# Groupe7.net
KiCad netlist of a schematic drawn in EAGLE
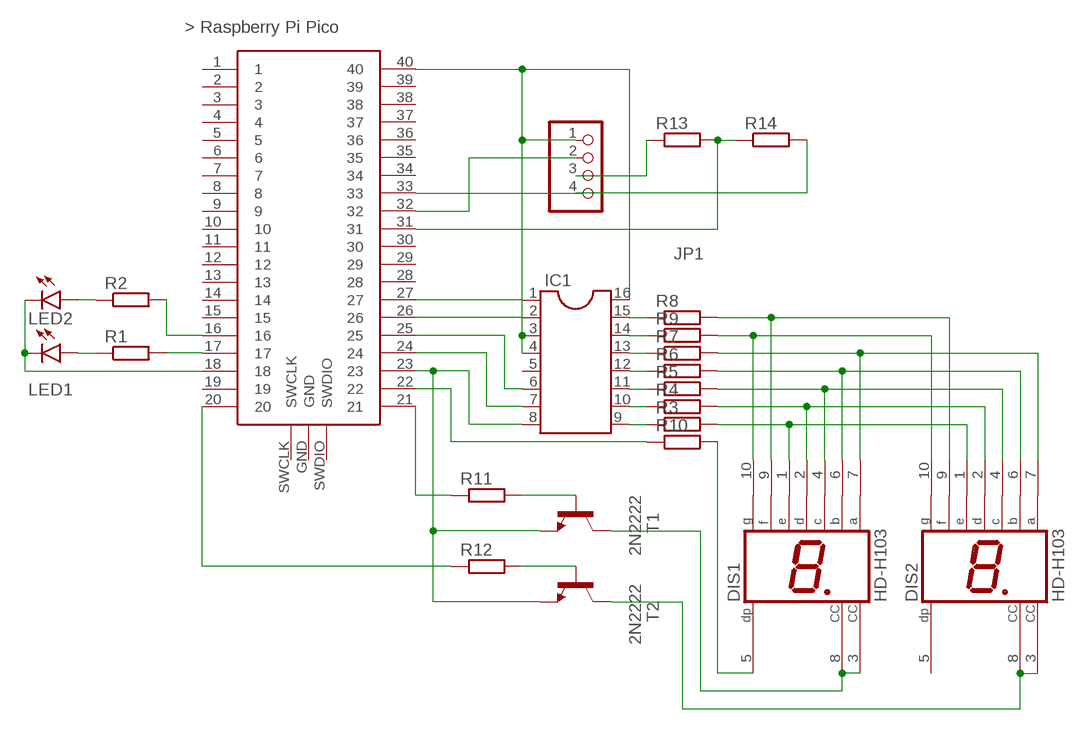
[diagram p0: schematic, sheet 1]

(export (version "E")
  (design (tool "Eeschema 10.0.6"))
  (components
    (comp (ref "DIS1")
      (value "HD-H103")
      (footprint "eagle-import:HDSP-M")
      (libsource (lib "eagle-import") (part "HD-H103"))
    )
    (comp (ref "DIS2")
      (value "HD-H103")
      (footprint "eagle-import:HDSP-M")
      (libsource (lib "eagle-import") (part "HD-H103"))
    )
    (comp (ref "IC1")
      (value "DIL16")
      (footprint "eagle-import:DIL16")
      (libsource (lib "eagle-import") (part "DIL16"))
    )
    (comp (ref "JP1")
      (value "PINHD-1X4")
      (footprint "eagle-import:1X04")
      (libsource (lib "eagle-import") (part "PINHD-1X4"))
    )
    (comp (ref "LED1")
      (value "LED5MM")
      (footprint "eagle-import:LED5MM")
      (libsource (lib "eagle-import") (part "LED5MM"))
    )
    (comp (ref "LED2")
      (value "LED5MM")
      (footprint "eagle-import:LED5MM")
      (libsource (lib "eagle-import") (part "LED5MM"))
    )
    (comp (ref "R1")
      (value "R-EU_0207/7")
      (footprint "eagle-import:0207_7")
      (libsource (lib "eagle-import") (part "R-EU_0207/7"))
    )
    (comp (ref "R2")
      (value "R-EU_0207/7")
      (footprint "eagle-import:0207_7")
      (libsource (lib "eagle-import") (part "R-EU_0207/7"))
    )
    (comp (ref "R3")
      (value "R-EU_0207/7")
      (footprint "eagle-import:0207_7")
      (libsource (lib "eagle-import") (part "R-EU_0207/7"))
    )
    (comp (ref "R4")
      (value "R-EU_0207/7")
      (footprint "eagle-import:0207_7")
      (libsource (lib "eagle-import") (part "R-EU_0207/7"))
    )
    (comp (ref "R5")
      (value "R-EU_0207/7")
      (footprint "eagle-import:0207_7")
      (libsource (lib "eagle-import") (part "R-EU_0207/7"))
    )
    (comp (ref "R6")
      (value "R-EU_0207/7")
      (footprint "eagle-import:0207_7")
      (libsource (lib "eagle-import") (part "R-EU_0207/7"))
    )
    (comp (ref "R7")
      (value "R-EU_0207/7")
      (footprint "eagle-import:0207_7")
      (libsource (lib "eagle-import") (part "R-EU_0207/7"))
    )
    (comp (ref "R8")
      (value "R-EU_0207/7")
      (footprint "eagle-import:0207_7")
      (libsource (lib "eagle-import") (part "R-EU_0207/7"))
    )
    (comp (ref "R9")
      (value "R-EU_0207/7")
      (footprint "eagle-import:0207_7")
      (libsource (lib "eagle-import") (part "R-EU_0207/7"))
    )
    (comp (ref "R10")
      (value "R-EU_0207/7")
      (footprint "eagle-import:0207_7")
      (libsource (lib "eagle-import") (part "R-EU_0207/7"))
    )
    (comp (ref "R11")
      (value "R-EU_0207/7")
      (footprint "eagle-import:0207_7")
      (libsource (lib "eagle-import") (part "R-EU_0207/7"))
    )
    (comp (ref "R12")
      (value "R-EU_0207/7")
      (footprint "eagle-import:0207_7")
      (libsource (lib "eagle-import") (part "R-EU_0207/7"))
    )
    (comp (ref "R13")
      (value "R-EU_0207/7")
      (footprint "eagle-import:0207_7")
      (libsource (lib "eagle-import") (part "R-EU_0207/7"))
    )
    (comp (ref "R14")
      (value "R-EU_0207/7")
      (footprint "eagle-import:0207_7")
      (libsource (lib "eagle-import") (part "R-EU_0207/7"))
    )
    (comp (ref "T1")
      (value "2N2222")
      (footprint "eagle-import:TO18")
      (libsource (lib "eagle-import") (part "2N2222"))
    )
    (comp (ref "T2")
      (value "2N2222")
      (footprint "eagle-import:TO18")
      (libsource (lib "eagle-import") (part "2N2222"))
    )
    (comp (ref "U$1")
      (value "RASPBERRY-PI-PICO_TH")
      (footprint "eagle-import:FT_RASPBERRY-PI-PICO_TH")
      (libsource (lib "eagle-import") (part "RASPBERRY-PI-PICO_TH"))
    )
  )
  (nets
    (net (code "1") (name "Net-(DIS1-A)") (class "Default")
      (node (ref "DIS1") (pin "7") (pinfunction "A_7") (pintype "passive"))
      (node (ref "DIS2") (pin "7") (pinfunction "A_7") (pintype "passive"))
      (node (ref "R7") (pin "2") (pinfunction "2_2") (pintype "passive"))
    )
    (net (code "2") (name "Net-(DIS1-B)") (class "Default")
      (node (ref "DIS1") (pin "6") (pinfunction "B_6") (pintype "passive"))
      (node (ref "DIS2") (pin "6") (pinfunction "B_6") (pintype "passive"))
      (node (ref "R6") (pin "2") (pinfunction "2_2") (pintype "passive"))
    )
    (net (code "3") (name "Net-(DIS1-C)") (class "Default")
      (node (ref "DIS1") (pin "4") (pinfunction "C_4") (pintype "passive"))
      (node (ref "DIS2") (pin "4") (pinfunction "C_4") (pintype "passive"))
      (node (ref "R5") (pin "2") (pinfunction "2_2") (pintype "passive"))
    )
    (net (code "4") (name "Net-(DIS1-D)") (class "Default")
      (node (ref "DIS1") (pin "2") (pinfunction "D_2") (pintype "passive"))
      (node (ref "DIS2") (pin "2") (pinfunction "D_2") (pintype "passive"))
      (node (ref "R4") (pin "2") (pinfunction "2_2") (pintype "passive"))
    )
    (net (code "5") (name "Net-(DIS1-DP)") (class "Default")
      (node (ref "DIS1") (pin "5") (pinfunction "DP_5") (pintype "passive"))
      (node (ref "R10") (pin "2") (pinfunction "2_2") (pintype "passive"))
    )
    (net (code "6") (name "Net-(DIS1-E)") (class "Default")
      (node (ref "DIS1") (pin "1") (pinfunction "E_1") (pintype "passive"))
      (node (ref "DIS2") (pin "1") (pinfunction "E_1") (pintype "passive"))
      (node (ref "R3") (pin "2") (pinfunction "2_2") (pintype "passive"))
    )
    (net (code "7") (name "Net-(DIS1-F)") (class "Default")
      (node (ref "DIS1") (pin "9") (pinfunction "F_9") (pintype "passive"))
      (node (ref "DIS2") (pin "9") (pinfunction "F_9") (pintype "passive"))
      (node (ref "R8") (pin "2") (pinfunction "2_2") (pintype "passive"))
    )
    (net (code "8") (name "Net-(DIS1-G)") (class "Default")
      (node (ref "DIS1") (pin "10") (pinfunction "G_10") (pintype "passive"))
      (node (ref "DIS2") (pin "10") (pinfunction "G_10") (pintype "passive"))
      (node (ref "R9") (pin "2") (pinfunction "2_2") (pintype "passive"))
    )
    (net (code "9") (name "Net-(IC1-Pad1)") (class "Default")
      (node (ref "IC1") (pin "1") (pinfunction "1_1") (pintype "passive"))
      (node (ref "U$1") (pin "27") (pinfunction "27_27") (pintype "bidirectional"))
    )
    (net (code "10") (name "Net-(IC1-Pad2)") (class "Default")
      (node (ref "IC1") (pin "2") (pinfunction "2_2") (pintype "passive"))
      (node (ref "U$1") (pin "26") (pinfunction "26_26") (pintype "bidirectional"))
    )
    (net (code "11") (name "Net-(IC1-Pad6)") (class "Default")
      (node (ref "IC1") (pin "6") (pinfunction "6_6") (pintype "passive"))
      (node (ref "U$1") (pin "25") (pinfunction "25_25") (pintype "bidirectional"))
    )
    (net (code "12") (name "Net-(IC1-Pad7)") (class "Default")
      (node (ref "IC1") (pin "7") (pinfunction "7_7") (pintype "passive"))
      (node (ref "U$1") (pin "24") (pinfunction "24_24") (pintype "bidirectional"))
    )
    (net (code "13") (name "Net-(IC1-Pad9)") (class "Default")
      (node (ref "IC1") (pin "9") (pinfunction "9_9") (pintype "passive"))
      (node (ref "R3") (pin "1") (pinfunction "1_1") (pintype "passive"))
    )
    (net (code "14") (name "Net-(IC1-Pad10)") (class "Default")
      (node (ref "IC1") (pin "10") (pinfunction "10_10") (pintype "passive"))
      (node (ref "R4") (pin "1") (pinfunction "1_1") (pintype "passive"))
    )
    (net (code "15") (name "Net-(IC1-Pad11)") (class "Default")
      (node (ref "IC1") (pin "11") (pinfunction "11_11") (pintype "passive"))
      (node (ref "R5") (pin "1") (pinfunction "1_1") (pintype "passive"))
    )
    (net (code "16") (name "Net-(IC1-Pad12)") (class "Default")
      (node (ref "IC1") (pin "12") (pinfunction "12_12") (pintype "passive"))
      (node (ref "R6") (pin "1") (pinfunction "1_1") (pintype "passive"))
    )
    (net (code "17") (name "Net-(IC1-Pad13)") (class "Default")
      (node (ref "IC1") (pin "13") (pinfunction "13_13") (pintype "passive"))
      (node (ref "R7") (pin "1") (pinfunction "1_1") (pintype "passive"))
    )
    (net (code "18") (name "Net-(IC1-Pad14)") (class "Default")
      (node (ref "IC1") (pin "14") (pinfunction "14_14") (pintype "passive"))
      (node (ref "R9") (pin "1") (pinfunction "1_1") (pintype "passive"))
    )
    (net (code "19") (name "Net-(IC1-Pad15)") (class "Default")
      (node (ref "IC1") (pin "15") (pinfunction "15_15") (pintype "passive"))
      (node (ref "R8") (pin "1") (pinfunction "1_1") (pintype "passive"))
    )
    (net (code "20") (name "Net-(IC1-Pad16)") (class "Default")
      (node (ref "IC1") (pin "16") (pinfunction "16_16") (pintype "passive"))
      (node (ref "IC1") (pin "3") (pinfunction "3_3") (pintype "passive"))
      (node (ref "IC1") (pin "4") (pinfunction "4_4") (pintype "passive"))
      (node (ref "JP1") (pin "1") (pinfunction "1_1") (pintype "passive"))
      (node (ref "U$1") (pin "40") (pinfunction "40_40") (pintype "bidirectional"))
    )
    (net (code "21") (name "Net-(JP1-Pad2)") (class "Default")
      (node (ref "JP1") (pin "2") (pinfunction "2_2") (pintype "passive"))
      (node (ref "U$1") (pin "32") (pinfunction "32_32") (pintype "bidirectional"))
    )
    (net (code "22") (name "Net-(JP1-Pad3)") (class "Default")
      (node (ref "JP1") (pin "3") (pinfunction "3_3") (pintype "passive"))
      (node (ref "R13") (pin "1") (pinfunction "1_1") (pintype "passive"))
    )
    (net (code "23") (name "Net-(JP1-Pad4)") (class "Default")
      (node (ref "JP1") (pin "4") (pinfunction "4_4") (pintype "passive"))
      (node (ref "R14") (pin "2") (pinfunction "2_2") (pintype "passive"))
      (node (ref "U$1") (pin "33") (pinfunction "33_33") (pintype "bidirectional"))
    )
    (net (code "24") (name "Net-(LED1-C)") (class "Default")
      (node (ref "LED1") (pin "K") (pinfunction "C_K") (pintype "passive"))
      (node (ref "LED2") (pin "K") (pinfunction "C_K") (pintype "passive"))
      (node (ref "U$1") (pin "18") (pinfunction "18_18") (pintype "bidirectional"))
    )
    (net (code "25") (name "Net-(LED1-PadA)") (class "Default")
      (node (ref "LED1") (pin "A") (pinfunction "A_A") (pintype "passive"))
      (node (ref "R1") (pin "1") (pinfunction "1_1") (pintype "passive"))
    )
    (net (code "26") (name "Net-(LED2-PadA)") (class "Default")
      (node (ref "LED2") (pin "A") (pinfunction "A_A") (pintype "passive"))
      (node (ref "R2") (pin "1") (pinfunction "1_1") (pintype "passive"))
    )
    (net (code "27") (name "Net-(R1-Pad2)") (class "Default")
      (node (ref "R1") (pin "2") (pinfunction "2_2") (pintype "passive"))
      (node (ref "U$1") (pin "17") (pinfunction "17_17") (pintype "bidirectional"))
    )
    (net (code "28") (name "Net-(R2-Pad2)") (class "Default")
      (node (ref "R2") (pin "2") (pinfunction "2_2") (pintype "passive"))
      (node (ref "U$1") (pin "16") (pinfunction "16_16") (pintype "bidirectional"))
    )
    (net (code "29") (name "Net-(R10-Pad1)") (class "Default")
      (node (ref "R10") (pin "1") (pinfunction "1_1") (pintype "passive"))
      (node (ref "U$1") (pin "22") (pinfunction "22_22") (pintype "bidirectional"))
    )
    (net (code "30") (name "Net-(R11-Pad1)") (class "Default")
      (node (ref "R11") (pin "1") (pinfunction "1_1") (pintype "passive"))
      (node (ref "U$1") (pin "21") (pinfunction "21_21") (pintype "bidirectional"))
    )
    (net (code "31") (name "Net-(R12-Pad1)") (class "Default")
      (node (ref "R12") (pin "1") (pinfunction "1_1") (pintype "passive"))
      (node (ref "U$1") (pin "20") (pinfunction "20_20") (pintype "bidirectional"))
    )
    (net (code "32") (name "Net-(R13-Pad2)") (class "Default")
      (node (ref "R13") (pin "2") (pinfunction "2_2") (pintype "passive"))
      (node (ref "R14") (pin "1") (pinfunction "1_1") (pintype "passive"))
      (node (ref "U$1") (pin "31") (pinfunction "31_31") (pintype "bidirectional"))
    )
    (net (code "33") (name "Net-(T1-B)") (class "Default")
      (node (ref "R11") (pin "2") (pinfunction "2_2") (pintype "passive"))
      (node (ref "T1") (pin "2") (pinfunction "B_2") (pintype "passive"))
    )
    (net (code "34") (name "Net-(T1-C)") (class "Default")
      (node (ref "DIS1") (pin "3") (pinfunction "CC_3") (pintype "passive"))
      (node (ref "DIS1") (pin "8") (pinfunction "CC_8") (pintype "passive"))
      (node (ref "T1") (pin "3") (pinfunction "C_3") (pintype "passive"))
    )
    (net (code "35") (name "Net-(T1-E)") (class "Default")
      (node (ref "IC1") (pin "8") (pinfunction "8_8") (pintype "passive"))
      (node (ref "T1") (pin "1") (pinfunction "E_1") (pintype "passive"))
      (node (ref "T2") (pin "1") (pinfunction "E_1") (pintype "passive"))
      (node (ref "U$1") (pin "23") (pinfunction "23_23") (pintype "bidirectional"))
    )
    (net (code "36") (name "Net-(T2-B)") (class "Default")
      (node (ref "R12") (pin "2") (pinfunction "2_2") (pintype "passive"))
      (node (ref "T2") (pin "2") (pinfunction "B_2") (pintype "passive"))
    )
    (net (code "37") (name "Net-(T2-C)") (class "Default")
      (node (ref "DIS2") (pin "3") (pinfunction "CC_3") (pintype "passive"))
      (node (ref "DIS2") (pin "8") (pinfunction "CC_8") (pintype "passive"))
      (node (ref "T2") (pin "3") (pinfunction "C_3") (pintype "passive"))
    )
    (net (code "38") (name "unconnected-(DIS2-DP-Pad5)") (class "Default")
      (node (ref "DIS2") (pin "5") (pinfunction "DP_5") (pintype "passive"))
    )
    (net (code "39") (name "unconnected-(IC1-Pad5)") (class "Default")
      (node (ref "IC1") (pin "5") (pinfunction "5_5") (pintype "passive"))
    )
    (net (code "40") (name "unconnected-(U$1-Pad1)") (class "Default")
      (node (ref "U$1") (pin "1") (pinfunction "1_1") (pintype "bidirectional"))
    )
    (net (code "41") (name "unconnected-(U$1-Pad2)") (class "Default")
      (node (ref "U$1") (pin "2") (pinfunction "2_2") (pintype "bidirectional"))
    )
    (net (code "42") (name "unconnected-(U$1-Pad3)") (class "Default")
      (node (ref "U$1") (pin "3") (pinfunction "3_3") (pintype "bidirectional"))
    )
    (net (code "43") (name "unconnected-(U$1-Pad4)") (class "Default")
      (node (ref "U$1") (pin "4") (pinfunction "4_4") (pintype "bidirectional"))
    )
    (net (code "44") (name "unconnected-(U$1-Pad5)") (class "Default")
      (node (ref "U$1") (pin "5") (pinfunction "5_5") (pintype "bidirectional"))
    )
    (net (code "45") (name "unconnected-(U$1-Pad6)") (class "Default")
      (node (ref "U$1") (pin "6") (pinfunction "6_6") (pintype "bidirectional"))
    )
    (net (code "46") (name "unconnected-(U$1-Pad7)") (class "Default")
      (node (ref "U$1") (pin "7") (pinfunction "7_7") (pintype "bidirectional"))
    )
    (net (code "47") (name "unconnected-(U$1-Pad8)") (class "Default")
      (node (ref "U$1") (pin "8") (pinfunction "8_8") (pintype "bidirectional"))
    )
    (net (code "48") (name "unconnected-(U$1-Pad9)") (class "Default")
      (node (ref "U$1") (pin "9") (pinfunction "9_9") (pintype "bidirectional"))
    )
    (net (code "49") (name "unconnected-(U$1-Pad10)") (class "Default")
      (node (ref "U$1") (pin "10") (pinfunction "10_10") (pintype "bidirectional"))
    )
    (net (code "50") (name "unconnected-(U$1-Pad11)") (class "Default")
      (node (ref "U$1") (pin "11") (pinfunction "11_11") (pintype "bidirectional"))
    )
    (net (code "51") (name "unconnected-(U$1-Pad12)") (class "Default")
      (node (ref "U$1") (pin "12") (pinfunction "12_12") (pintype "bidirectional"))
    )
    (net (code "52") (name "unconnected-(U$1-Pad13)") (class "Default")
      (node (ref "U$1") (pin "13") (pinfunction "13_13") (pintype "bidirectional"))
    )
    (net (code "53") (name "unconnected-(U$1-Pad14)") (class "Default")
      (node (ref "U$1") (pin "14") (pinfunction "14_14") (pintype "bidirectional"))
    )
    (net (code "54") (name "unconnected-(U$1-Pad15)") (class "Default")
      (node (ref "U$1") (pin "15") (pinfunction "15_15") (pintype "bidirectional"))
    )
    (net (code "55") (name "unconnected-(U$1-Pad19)") (class "Default")
      (node (ref "U$1") (pin "19") (pinfunction "19_19") (pintype "bidirectional"))
    )
    (net (code "56") (name "unconnected-(U$1-Pad28)") (class "Default")
      (node (ref "U$1") (pin "28") (pinfunction "28_28") (pintype "bidirectional"))
    )
    (net (code "57") (name "unconnected-(U$1-Pad29)") (class "Default")
      (node (ref "U$1") (pin "29") (pinfunction "29_29") (pintype "bidirectional"))
    )
    (net (code "58") (name "unconnected-(U$1-Pad30)") (class "Default")
      (node (ref "U$1") (pin "30") (pinfunction "30_30") (pintype "bidirectional"))
    )
    (net (code "59") (name "unconnected-(U$1-Pad34)") (class "Default")
      (node (ref "U$1") (pin "34") (pinfunction "34_34") (pintype "bidirectional"))
    )
    (net (code "60") (name "unconnected-(U$1-Pad35)") (class "Default")
      (node (ref "U$1") (pin "35") (pinfunction "35_35") (pintype "bidirectional"))
    )
    (net (code "61") (name "unconnected-(U$1-Pad36)") (class "Default")
      (node (ref "U$1") (pin "36") (pinfunction "36_36") (pintype "bidirectional"))
    )
    (net (code "62") (name "unconnected-(U$1-Pad37)") (class "Default")
      (node (ref "U$1") (pin "37") (pinfunction "37_37") (pintype "bidirectional"))
    )
    (net (code "63") (name "unconnected-(U$1-Pad38)") (class "Default")
      (node (ref "U$1") (pin "38") (pinfunction "38_38") (pintype "bidirectional"))
    )
    (net (code "64") (name "unconnected-(U$1-Pad39)") (class "Default")
      (node (ref "U$1") (pin "39") (pinfunction "39_39") (pintype "bidirectional"))
    )
    (net (code "65") (name "unconnected-(U$1-PadGND)") (class "Default")
      (node (ref "U$1") (pin "GND") (pinfunction "GND_GND") (pintype "bidirectional"))
    )
    (net (code "66") (name "unconnected-(U$1-PadSWCLK)") (class "Default")
      (node (ref "U$1") (pin "SWCLK") (pinfunction "SWCLK_SWCLK") (pintype "bidirectional"))
    )
    (net (code "67") (name "unconnected-(U$1-PadSWDIO)") (class "Default")
      (node (ref "U$1") (pin "SWDIO") (pinfunction "SWDIO_SWDIO") (pintype "bidirectional"))
    )
  )
)
